# Gravador_ISP.net
KiCad netlist of a schematic drawn in EAGLE
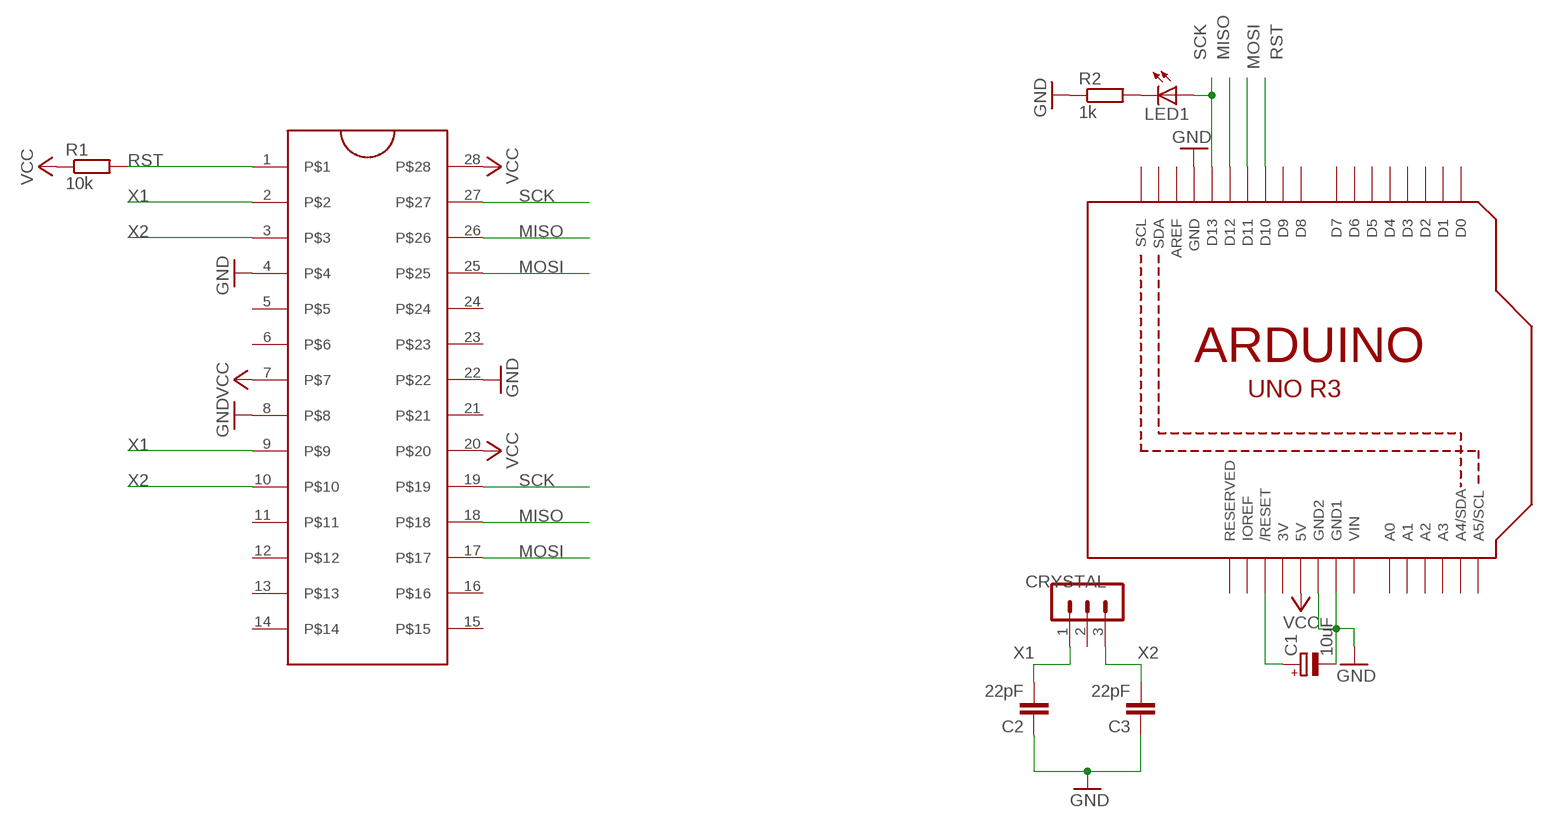
[diagram p0: schematic, sheet 1]

(export (version "E")
  (design (tool "Eeschema 10.0.6"))
  (components
    (comp (ref "C1")
      (value "10uF")
      (footprint "eagle-import:E2,5-5")
      (libsource (lib "eagle-import") (part "CPOL-EUE2.5-5"))
    )
    (comp (ref "C2")
      (value "22pF")
      (footprint "eagle-import:C050-024X044")
      (libsource (lib "eagle-import") (part "C-EU050-024X044"))
    )
    (comp (ref "C3")
      (value "22pF")
      (footprint "eagle-import:C050-024X044")
      (libsource (lib "eagle-import") (part "C-EU050-024X044"))
    )
    (comp (ref "CRYSTAL")
      (value "MA03-1")
      (footprint "eagle-import:MA03-1")
      (libsource (lib "eagle-import") (part "MA03-1"))
    )
    (comp (ref "J1")
      (value "ZIFSOCKET-28-3\"")
      (footprint "eagle-import:DIL28-3-ZIF_SOCKET")
      (libsource (lib "eagle-import") (part "ZIFSOCKET-28-3{dblquote}"))
    )
    (comp (ref "LED1")
      (value "LED3MM")
      (footprint "eagle-import:LED3MM")
      (libsource (lib "eagle-import") (part "LED3MM"))
    )
    (comp (ref "R1")
      (value "10k")
      (footprint "eagle-import:0207_10")
      (libsource (lib "eagle-import") (part "R-EU_0207/10"))
    )
    (comp (ref "R2")
      (value "1k")
      (footprint "eagle-import:0207_10")
      (libsource (lib "eagle-import") (part "R-EU_0207/10"))
    )
    (comp (ref "U1")
      (value "ARDUINOR3-DIMENSION")
      (footprint "eagle-import:ARDUINOR3")
      (libsource (lib "eagle-import") (part "ARDUINOR3-DIMENSION"))
    )
  )
  (nets
    (net (code "1") (name "/3V") (class "Default")
      (node (ref "U1") (pin "3V") (pinfunction "3V_3V") (pintype "power_in"))
    )
    (net (code "2") (name "/MISO") (class "Default")
      (node (ref "J1") (pin "18") (pinfunction "P$18_18") (pintype "bidirectional"))
      (node (ref "J1") (pin "26") (pinfunction "P$26_26") (pintype "bidirectional"))
      (node (ref "U1") (pin "D12") (pinfunction "D12_D12") (pintype "bidirectional"))
    )
    (net (code "3") (name "/MOSI") (class "Default")
      (node (ref "J1") (pin "17") (pinfunction "P$17_17") (pintype "bidirectional"))
      (node (ref "J1") (pin "25") (pinfunction "P$25_25") (pintype "bidirectional"))
      (node (ref "U1") (pin "D11") (pinfunction "D11_D11") (pintype "bidirectional"))
    )
    (net (code "4") (name "/RST") (class "Default")
      (node (ref "J1") (pin "1") (pinfunction "P$1_1") (pintype "bidirectional"))
      (node (ref "R1") (pin "2") (pinfunction "2_2") (pintype "passive"))
      (node (ref "U1") (pin "D10") (pinfunction "D10_D10") (pintype "bidirectional"))
    )
    (net (code "5") (name "/SCK") (class "Default")
      (node (ref "J1") (pin "19") (pinfunction "P$19_19") (pintype "bidirectional"))
      (node (ref "J1") (pin "27") (pinfunction "P$27_27") (pintype "bidirectional"))
      (node (ref "LED1") (pin "A") (pinfunction "A_A") (pintype "passive"))
      (node (ref "U1") (pin "D13") (pinfunction "D13_D13") (pintype "bidirectional"))
    )
    (net (code "6") (name "/VIN") (class "Default")
      (node (ref "U1") (pin "VIN") (pinfunction "VIN_VIN") (pintype "power_in"))
    )
    (net (code "7") (name "/X1") (class "Default")
      (node (ref "C2") (pin "2") (pinfunction "2_2") (pintype "passive"))
      (node (ref "CRYSTAL") (pin "1") (pinfunction "1_1") (pintype "passive"))
      (node (ref "J1") (pin "2") (pinfunction "P$2_2") (pintype "bidirectional"))
      (node (ref "J1") (pin "9") (pinfunction "P$9_9") (pintype "bidirectional"))
    )
    (net (code "8") (name "/X2") (class "Default")
      (node (ref "C3") (pin "2") (pinfunction "2_2") (pintype "passive"))
      (node (ref "CRYSTAL") (pin "3") (pinfunction "3_3") (pintype "passive"))
      (node (ref "J1") (pin "10") (pinfunction "P$10_10") (pintype "bidirectional"))
      (node (ref "J1") (pin "3") (pinfunction "P$3_3") (pintype "bidirectional"))
    )
    (net (code "9") (name "GND") (class "Default")
      (node (ref "C1") (pin "-") (pinfunction "-_-") (pintype "passive"))
      (node (ref "C2") (pin "1") (pinfunction "1_1") (pintype "passive"))
      (node (ref "C3") (pin "1") (pinfunction "1_1") (pintype "passive"))
      (node (ref "J1") (pin "22") (pinfunction "P$22_22") (pintype "bidirectional"))
      (node (ref "J1") (pin "4") (pinfunction "P$4_4") (pintype "bidirectional"))
      (node (ref "J1") (pin "8") (pinfunction "P$8_8") (pintype "bidirectional"))
      (node (ref "R2") (pin "1") (pinfunction "1_1") (pintype "passive"))
      (node (ref "U1") (pin "GND") (pinfunction "GND_GND") (pintype "power_in"))
      (node (ref "U1") (pin "GND1") (pinfunction "GND1_GND1") (pintype "power_in"))
      (node (ref "U1") (pin "GND2") (pinfunction "GND2_GND2") (pintype "power_in"))
    )
    (net (code "10") (name "Net-(LED1-C)") (class "Default")
      (node (ref "LED1") (pin "K") (pinfunction "C_K") (pintype "passive"))
      (node (ref "R2") (pin "2") (pinfunction "2_2") (pintype "passive"))
    )
    (net (code "11") (name "Net-(U1-{slash}RESET)") (class "Default")
      (node (ref "C1") (pin "+") (pinfunction "+_+") (pintype "passive"))
      (node (ref "U1") (pin "RESET") (pinfunction "/RESET_RESET") (pintype "bidirectional"))
    )
    (net (code "12") (name "VCC") (class "Default")
      (node (ref "J1") (pin "20") (pinfunction "P$20_20") (pintype "bidirectional"))
      (node (ref "J1") (pin "28") (pinfunction "P$28_28") (pintype "bidirectional"))
      (node (ref "J1") (pin "7") (pinfunction "P$7_7") (pintype "bidirectional"))
      (node (ref "R1") (pin "1") (pinfunction "1_1") (pintype "passive"))
      (node (ref "U1") (pin "5V") (pinfunction "5V_5V") (pintype "power_in"))
    )
    (net (code "13") (name "unconnected-(CRYSTAL-Pad2)") (class "Default")
      (node (ref "CRYSTAL") (pin "2") (pinfunction "2_2") (pintype "passive"))
    )
    (net (code "14") (name "unconnected-(J1-P$5-Pad5)") (class "Default")
      (node (ref "J1") (pin "5") (pinfunction "P$5_5") (pintype "bidirectional"))
    )
    (net (code "15") (name "unconnected-(J1-P$6-Pad6)") (class "Default")
      (node (ref "J1") (pin "6") (pinfunction "P$6_6") (pintype "bidirectional"))
    )
    (net (code "16") (name "unconnected-(J1-P$11-Pad11)") (class "Default")
      (node (ref "J1") (pin "11") (pinfunction "P$11_11") (pintype "bidirectional"))
    )
    (net (code "17") (name "unconnected-(J1-P$12-Pad12)") (class "Default")
      (node (ref "J1") (pin "12") (pinfunction "P$12_12") (pintype "bidirectional"))
    )
    (net (code "18") (name "unconnected-(J1-P$13-Pad13)") (class "Default")
      (node (ref "J1") (pin "13") (pinfunction "P$13_13") (pintype "bidirectional"))
    )
    (net (code "19") (name "unconnected-(J1-P$14-Pad14)") (class "Default")
      (node (ref "J1") (pin "14") (pinfunction "P$14_14") (pintype "bidirectional"))
    )
    (net (code "20") (name "unconnected-(J1-P$15-Pad15)") (class "Default")
      (node (ref "J1") (pin "15") (pinfunction "P$15_15") (pintype "bidirectional"))
    )
    (net (code "21") (name "unconnected-(J1-P$16-Pad16)") (class "Default")
      (node (ref "J1") (pin "16") (pinfunction "P$16_16") (pintype "bidirectional"))
    )
    (net (code "22") (name "unconnected-(J1-P$21-Pad21)") (class "Default")
      (node (ref "J1") (pin "21") (pinfunction "P$21_21") (pintype "bidirectional"))
    )
    (net (code "23") (name "unconnected-(J1-P$23-Pad23)") (class "Default")
      (node (ref "J1") (pin "23") (pinfunction "P$23_23") (pintype "bidirectional"))
    )
    (net (code "24") (name "unconnected-(J1-P$24-Pad24)") (class "Default")
      (node (ref "J1") (pin "24") (pinfunction "P$24_24") (pintype "bidirectional"))
    )
    (net (code "25") (name "unconnected-(U1-A4{slash}SDA-PadA4)") (class "Default")
      (node (ref "U1") (pin "A4") (pinfunction "A4/SDA_A4") (pintype "bidirectional"))
    )
    (net (code "26") (name "unconnected-(U1-A5{slash}SCL-PadA5)") (class "Default")
      (node (ref "U1") (pin "A5") (pinfunction "A5/SCL_A5") (pintype "bidirectional"))
    )
    (net (code "27") (name "unconnected-(U1-PadA0)") (class "Default")
      (node (ref "U1") (pin "A0") (pinfunction "A0_A0") (pintype "bidirectional"))
    )
    (net (code "28") (name "unconnected-(U1-PadA1)") (class "Default")
      (node (ref "U1") (pin "A1") (pinfunction "A1_A1") (pintype "bidirectional"))
    )
    (net (code "29") (name "unconnected-(U1-PadA2)") (class "Default")
      (node (ref "U1") (pin "A2") (pinfunction "A2_A2") (pintype "bidirectional"))
    )
    (net (code "30") (name "unconnected-(U1-PadA3)") (class "Default")
      (node (ref "U1") (pin "A3") (pinfunction "A3_A3") (pintype "bidirectional"))
    )
    (net (code "31") (name "unconnected-(U1-PadAREF)") (class "Default")
      (node (ref "U1") (pin "AREF") (pinfunction "AREF_AREF") (pintype "bidirectional"))
    )
    (net (code "32") (name "unconnected-(U1-PadD0)") (class "Default")
      (node (ref "U1") (pin "D0") (pinfunction "D0_D0") (pintype "bidirectional"))
    )
    (net (code "33") (name "unconnected-(U1-PadD1)") (class "Default")
      (node (ref "U1") (pin "D1") (pinfunction "D1_D1") (pintype "bidirectional"))
    )
    (net (code "34") (name "unconnected-(U1-PadD2)") (class "Default")
      (node (ref "U1") (pin "D2") (pinfunction "D2_D2") (pintype "bidirectional"))
    )
    (net (code "35") (name "unconnected-(U1-PadD3)") (class "Default")
      (node (ref "U1") (pin "D3") (pinfunction "D3_D3") (pintype "bidirectional"))
    )
    (net (code "36") (name "unconnected-(U1-PadD4)") (class "Default")
      (node (ref "U1") (pin "D4") (pinfunction "D4_D4") (pintype "bidirectional"))
    )
    (net (code "37") (name "unconnected-(U1-PadD5)") (class "Default")
      (node (ref "U1") (pin "D5") (pinfunction "D5_D5") (pintype "bidirectional"))
    )
    (net (code "38") (name "unconnected-(U1-PadD6)") (class "Default")
      (node (ref "U1") (pin "D6") (pinfunction "D6_D6") (pintype "bidirectional"))
    )
    (net (code "39") (name "unconnected-(U1-PadD7)") (class "Default")
      (node (ref "U1") (pin "D7") (pinfunction "D7_D7") (pintype "bidirectional"))
    )
    (net (code "40") (name "unconnected-(U1-PadD8)") (class "Default")
      (node (ref "U1") (pin "D8") (pinfunction "D8_D8") (pintype "bidirectional"))
    )
    (net (code "41") (name "unconnected-(U1-PadD9)") (class "Default")
      (node (ref "U1") (pin "D9") (pinfunction "D9_D9") (pintype "bidirectional"))
    )
    (net (code "42") (name "unconnected-(U1-PadIOREF)") (class "Default")
      (node (ref "U1") (pin "IOREF") (pinfunction "IOREF_IOREF") (pintype "output"))
    )
    (net (code "43") (name "unconnected-(U1-PadRESERVED)") (class "Default")
      (node (ref "U1") (pin "RESERVED") (pinfunction "RESERVED_RESERVED") (pintype "no_connect"))
    )
    (net (code "44") (name "unconnected-(U1-PadSCL)") (class "Default")
      (node (ref "U1") (pin "SCL") (pinfunction "SCL_SCL") (pintype "bidirectional"))
    )
    (net (code "45") (name "unconnected-(U1-PadSDA)") (class "Default")
      (node (ref "U1") (pin "SDA") (pinfunction "SDA_SDA") (pintype "bidirectional"))
    )
  )
)
